# UART.net
KiCad netlist of a schematic drawn in Altium Designer
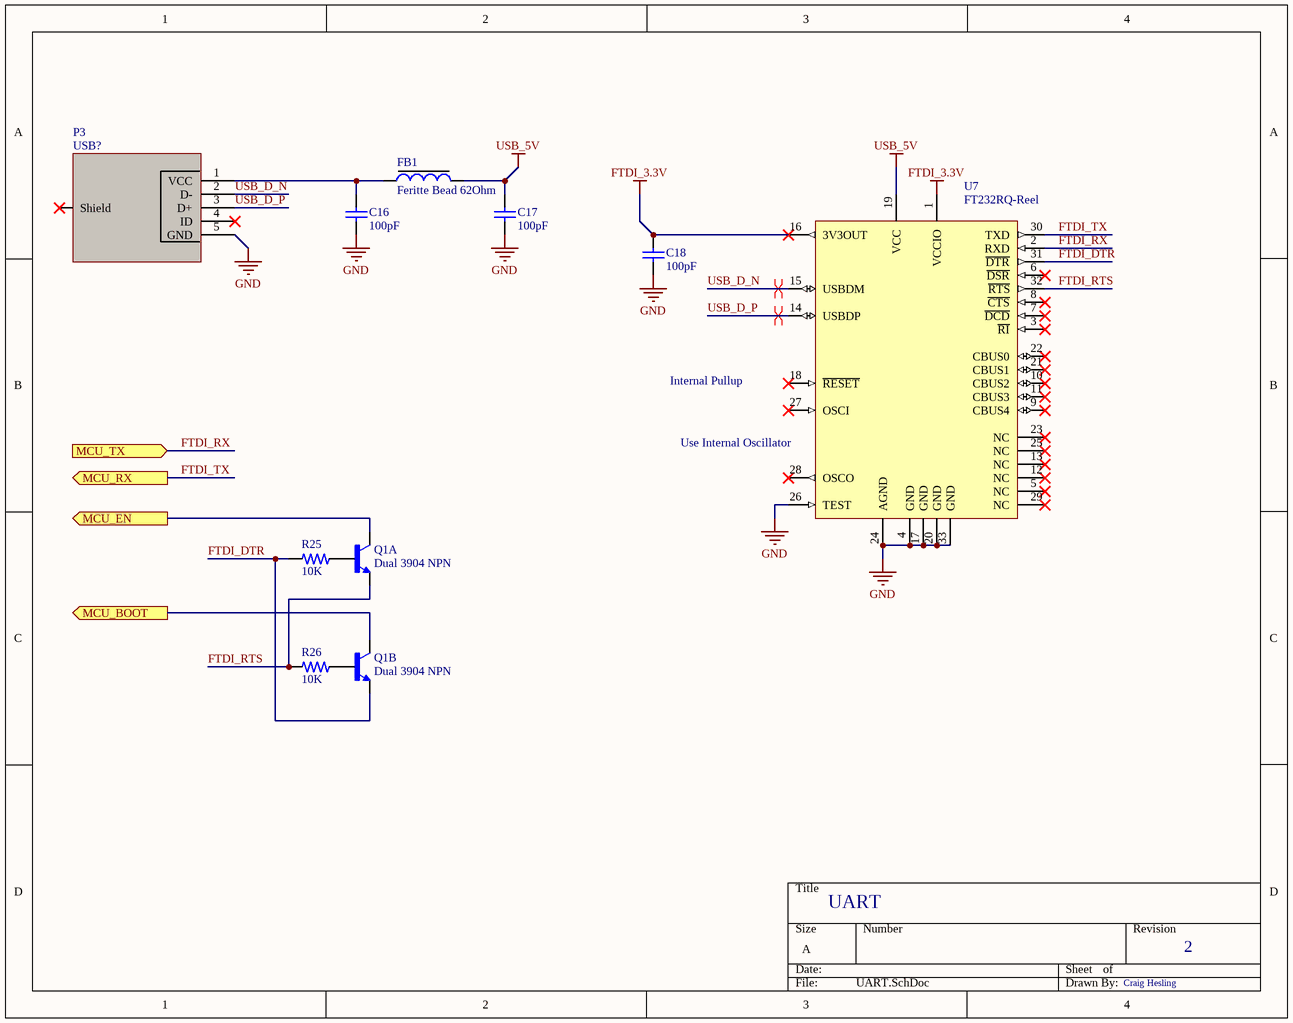
[diagram p0: UART.SchDoc]

(export (version "E")
  (design (tool "Eeschema 10.0.6"))
  (components
    (comp (ref "C16")
      (value "100pF")
      (footprint "CAPC1608X09L - CAP0603")
      (description "SMT 0603 Ceramic Capacitor")
      (fields (field (name "TOLERANCE") "5%") (field (name "VOLTAGE") "50V"))
      (libsource (lib "Passives") (part "CAP0603 100pF 5% 50V NP0"))
    )
    (comp (ref "C17")
      (value "100pF")
      (footprint "CAPC1608X09L - CAP0603")
      (description "SMT 0603 Ceramic Capacitor")
      (fields (field (name "TOLERANCE") "5%") (field (name "VOLTAGE") "50V"))
      (libsource (lib "Passives") (part "CAP0603 100pF 5% 50V NP0"))
    )
    (comp (ref "C18")
      (value "100pF")
      (footprint "CAPC1608X09L - CAP0603")
      (description "SMT 0603 Ceramic Capacitor")
      (fields (field (name "TOLERANCE") "5%") (field (name "VOLTAGE") "50V"))
      (libsource (lib "Passives") (part "CAP0603 100pF 5% 50V NP0"))
    )
    (comp (ref "FB1")
      (value "Feritte Bead 62Ohm")
      (footprint "INDC1608X10L - FL0603")
      (libsource (lib "Passives") (part "FB0603 62Ohm"))
    )
    (comp (ref "P3")
      (value "USB?")
      (footprint "MicroUSB_TypeB")
      (description "Micro USB Type B Port")
      (libsource (lib "Connectors") (part "MicroUSB TypeB"))
    )
    (comp (ref "Q1")
      (value "Dual 3904 NPN")
      (footprint "SOT65P210X110-6L")
      (description "3904 Dual NPN Transistor")
      (libsource (lib "Actives") (part "MBT3904DW1T1G"))
    )
    (comp (ref "R25")
      (value "10K")
      (footprint "RESC1608X06L - RES0603")
      (description "SMT 0603 Ceramic Resistor")
      (fields (field (name "POWER") "1/10W") (field (name "TOLERANCE") "1%"))
      (libsource (lib "Passives") (part "RES0603 10K 1% 1/10W"))
    )
    (comp (ref "R26")
      (value "10K")
      (footprint "RESC1608X06L - RES0603")
      (description "SMT 0603 Ceramic Resistor")
      (fields (field (name "POWER") "1/10W") (field (name "TOLERANCE") "1%"))
      (libsource (lib "Passives") (part "RES0603 10K 1% 1/10W"))
    )
    (comp (ref "U7")
      (value "FT232RQ-Reel")
      (footprint "PQFN5X5-32_V_FTDI_BIG_VIAS_LEADS")
      (description "USB UART Asynchronous Serial Data Transfer Chip, 32-pin QFN, Tape and Reel")
      (fields (field (name "MANUFACTURER") "FTDI"))
      (libsource (lib "Actives") (part "FT232RQ-Reel"))
    )
  )
  (nets
    (net (code "1") (name "/FTDI_DTR") (class "Default")
      (node (ref "Q1") (pin "1") (pinfunction "E2_1") (pintype "passive"))
      (node (ref "R25") (pin "2") (pinfunction "2_2") (pintype "passive"))
      (node (ref "U7") (pin "31") (pinfunction "~{DTR}_31") (pintype "output"))
    )
    (net (code "2") (name "/FTDI_RTS") (class "Default")
      (node (ref "Q1") (pin "4") (pinfunction "E1_4") (pintype "passive"))
      (node (ref "R26") (pin "2") (pinfunction "2_2") (pintype "passive"))
      (node (ref "U7") (pin "32") (pinfunction "~{RTS}_32") (pintype "output"))
    )
    (net (code "3") (name "/FTDI_RX") (class "Default")
      (node (ref "U7") (pin "2") (pinfunction "RXD_2") (pintype "input"))
    )
    (net (code "4") (name "/FTDI_TX") (class "Default")
      (node (ref "U7") (pin "30") (pinfunction "TXD_30") (pintype "output"))
    )
    (net (code "5") (name "/MCU_BOOT") (class "Default")
      (node (ref "Q1") (pin "6") (pinfunction "C2_6") (pintype "passive"))
    )
    (net (code "6") (name "/MCU_EN") (class "Default")
      (node (ref "Q1") (pin "3") (pinfunction "C1_3") (pintype "passive"))
    )
    (net (code "7") (name "/USB_D_N") (class "Default")
      (node (ref "P3") (pin "2") (pinfunction "D-_2") (pintype "passive"))
      (node (ref "U7") (pin "15") (pinfunction "USBDM_15") (pintype "bidirectional"))
    )
    (net (code "8") (name "/USB_D_P") (class "Default")
      (node (ref "P3") (pin "3") (pinfunction "D+_3") (pintype "passive"))
      (node (ref "U7") (pin "14") (pinfunction "USBDP_14") (pintype "bidirectional"))
    )
    (net (code "9") (name "FTDI_3.3V") (class "Default")
      (node (ref "C18") (pin "2") (pinfunction "2_2") (pintype "passive"))
      (node (ref "U7") (pin "1") (pinfunction "VCCIO_1") (pintype "power_in"))
      (node (ref "U7") (pin "16") (pinfunction "3V3OUT_16") (pintype "output"))
    )
    (net (code "10") (name "GND") (class "Default")
      (node (ref "C16") (pin "1") (pinfunction "1_1") (pintype "passive"))
      (node (ref "C17") (pin "1") (pinfunction "1_1") (pintype "passive"))
      (node (ref "C18") (pin "1") (pinfunction "1_1") (pintype "passive"))
      (node (ref "P3") (pin "5") (pinfunction "GND_5") (pintype "passive"))
      (node (ref "U7") (pin "17") (pinfunction "GND_17") (pintype "power_in"))
      (node (ref "U7") (pin "20") (pinfunction "GND_20") (pintype "power_in"))
      (node (ref "U7") (pin "24") (pinfunction "AGND_24") (pintype "power_in"))
      (node (ref "U7") (pin "26") (pinfunction "TEST_26") (pintype "input"))
      (node (ref "U7") (pin "33") (pinfunction "GND_33") (pintype "power_in"))
      (node (ref "U7") (pin "4") (pinfunction "GND_4") (pintype "power_in"))
    )
    (net (code "11") (name "Net-(P3-VCC)") (class "Default")
      (node (ref "C16") (pin "2") (pinfunction "2_2") (pintype "passive"))
      (node (ref "FB1") (pin "1") (pinfunction "1_1") (pintype "passive"))
      (node (ref "P3") (pin "1") (pinfunction "VCC_1") (pintype "passive"))
    )
    (net (code "12") (name "Net-(Q1A-B1)") (class "Default")
      (node (ref "Q1") (pin "5") (pinfunction "B1_5") (pintype "passive"))
      (node (ref "R25") (pin "1") (pinfunction "1_1") (pintype "passive"))
    )
    (net (code "13") (name "Net-(Q1B-B2)") (class "Default")
      (node (ref "Q1") (pin "2") (pinfunction "B2_2") (pintype "passive"))
      (node (ref "R26") (pin "1") (pinfunction "1_1") (pintype "passive"))
    )
    (net (code "14") (name "USB_5V") (class "Default")
      (node (ref "C17") (pin "2") (pinfunction "2_2") (pintype "passive"))
      (node (ref "FB1") (pin "2") (pinfunction "2_2") (pintype "passive"))
      (node (ref "U7") (pin "19") (pinfunction "VCC_19") (pintype "power_in"))
    )
    (net (code "15") (name "unconnected-(P3-ID-Pad4)") (class "Default")
      (node (ref "P3") (pin "4") (pinfunction "ID_4") (pintype "passive+no_connect"))
    )
    (net (code "16") (name "unconnected-(P3-Shield-Pad0)") (class "Default")
      (node (ref "P3") (pin "0") (pinfunction "Shield_0") (pintype "passive+no_connect"))
    )
    (net (code "17") (name "unconnected-(U7-CBUS0-Pad22)") (class "Default")
      (node (ref "U7") (pin "22") (pinfunction "CBUS0_22") (pintype "bidirectional+no_connect"))
    )
    (net (code "18") (name "unconnected-(U7-CBUS1-Pad21)") (class "Default")
      (node (ref "U7") (pin "21") (pinfunction "CBUS1_21") (pintype "bidirectional+no_connect"))
    )
    (net (code "19") (name "unconnected-(U7-CBUS2-Pad10)") (class "Default")
      (node (ref "U7") (pin "10") (pinfunction "CBUS2_10") (pintype "bidirectional+no_connect"))
    )
    (net (code "20") (name "unconnected-(U7-CBUS3-Pad11)") (class "Default")
      (node (ref "U7") (pin "11") (pinfunction "CBUS3_11") (pintype "bidirectional+no_connect"))
    )
    (net (code "21") (name "unconnected-(U7-CBUS4-Pad9)") (class "Default")
      (node (ref "U7") (pin "9") (pinfunction "CBUS4_9") (pintype "bidirectional+no_connect"))
    )
    (net (code "22") (name "unconnected-(U7-NC-Pad5)") (class "Default")
      (node (ref "U7") (pin "5") (pinfunction "NC_5") (pintype "passive+no_connect"))
    )
    (net (code "23") (name "unconnected-(U7-NC-Pad12)") (class "Default")
      (node (ref "U7") (pin "12") (pinfunction "NC_12") (pintype "passive+no_connect"))
    )
    (net (code "24") (name "unconnected-(U7-NC-Pad13)") (class "Default")
      (node (ref "U7") (pin "13") (pinfunction "NC_13") (pintype "passive+no_connect"))
    )
    (net (code "25") (name "unconnected-(U7-NC-Pad23)") (class "Default")
      (node (ref "U7") (pin "23") (pinfunction "NC_23") (pintype "passive+no_connect"))
    )
    (net (code "26") (name "unconnected-(U7-NC-Pad25)") (class "Default")
      (node (ref "U7") (pin "25") (pinfunction "NC_25") (pintype "passive+no_connect"))
    )
    (net (code "27") (name "unconnected-(U7-NC-Pad29)") (class "Default")
      (node (ref "U7") (pin "29") (pinfunction "NC_29") (pintype "passive+no_connect"))
    )
    (net (code "28") (name "unconnected-(U7-OSCI-Pad27)") (class "Default")
      (node (ref "U7") (pin "27") (pinfunction "OSCI_27") (pintype "input+no_connect"))
    )
    (net (code "29") (name "unconnected-(U7-OSCO-Pad28)") (class "Default")
      (node (ref "U7") (pin "28") (pinfunction "OSCO_28") (pintype "output+no_connect"))
    )
    (net (code "30") (name "unconnected-(U7-~{CTS}-Pad8)") (class "Default")
      (node (ref "U7") (pin "8") (pinfunction "~{CTS}_8") (pintype "input+no_connect"))
    )
    (net (code "31") (name "unconnected-(U7-~{DCD}-Pad7)") (class "Default")
      (node (ref "U7") (pin "7") (pinfunction "~{DCD}_7") (pintype "input+no_connect"))
    )
    (net (code "32") (name "unconnected-(U7-~{DSR}-Pad6)") (class "Default")
      (node (ref "U7") (pin "6") (pinfunction "~{DSR}_6") (pintype "input+no_connect"))
    )
    (net (code "33") (name "unconnected-(U7-~{RESET}-Pad18)") (class "Default")
      (node (ref "U7") (pin "18") (pinfunction "~{RESET}_18") (pintype "input+no_connect"))
    )
    (net (code "34") (name "unconnected-(U7-~{RI}-Pad3)") (class "Default")
      (node (ref "U7") (pin "3") (pinfunction "~{RI}_3") (pintype "input+no_connect"))
    )
  )
)
